# 13-UART_CAN_IO.net
KiCad netlist of a schematic drawn in Altium Designer
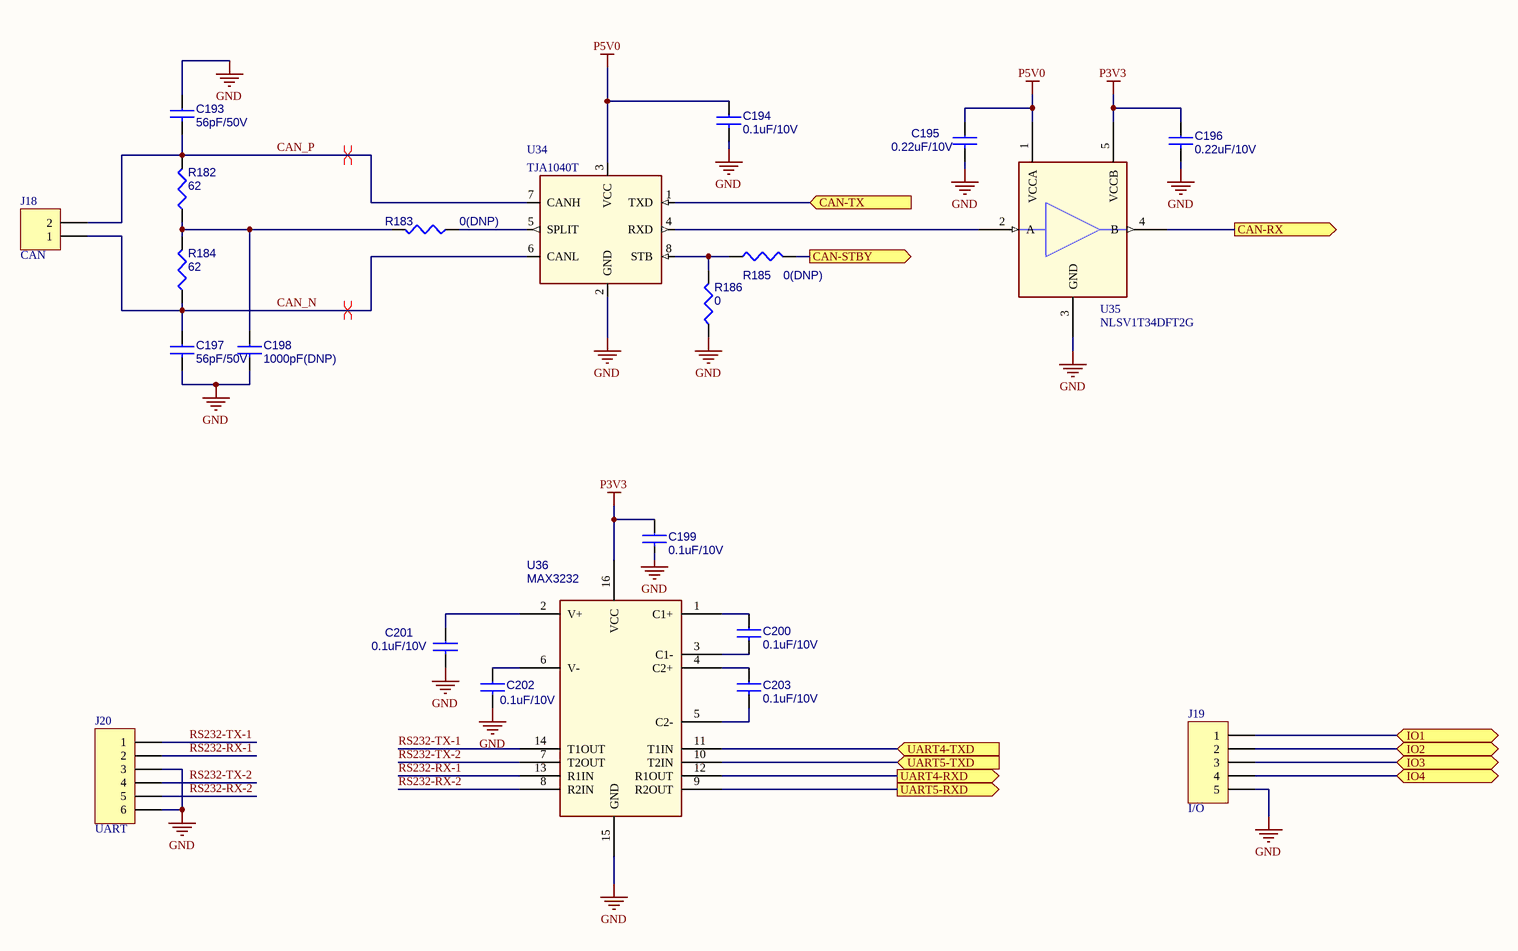
[diagram p0: 13-UART_CAN_IO.SchDoc]

(export (version "E")
  (design (tool "Eeschema 10.0.6"))
  (components
    (comp (ref "C193") (value "56pF/50V") (libsource (lib "*") (part "P_CAP NP")))
    (comp (ref "C194") (value "0.1uF/10V") (libsource (lib "*") (part "P_CAP NP")))
    (comp (ref "C195") (value "0.22uF/10V") (libsource (lib "*") (part "P_CAP NP")))
    (comp (ref "C196") (value "0.22uF/10V") (libsource (lib "*") (part "P_CAP NP")))
    (comp (ref "C197") (value "56pF/50V") (libsource (lib "*") (part "P_CAP NP")))
    (comp (ref "C198") (value "1000pF(DNP)") (libsource (lib "*") (part "P_CAP NP")))
    (comp (ref "C199") (value "0.1uF/10V") (libsource (lib "*") (part "CAP")))
    (comp (ref "C200") (value "0.1uF/10V") (libsource (lib "*") (part "CAP")))
    (comp (ref "C201") (value "0.1uF/10V") (libsource (lib "*") (part "CAP")))
    (comp (ref "C202") (value "0.1uF/10V") (libsource (lib "*") (part "CAP")))
    (comp (ref "C203") (value "0.1uF/10V") (libsource (lib "*") (part "CAP")))
    (comp (ref "J18")
      (value "CAN")
      (footprint "CON-2PIN")
      (description "Header, 2-Pin")
      (fields (field (name "PUBLISHER") "Altium Limited"))
      (libsource (lib "Miscellaneous Connectors") (part "Header 2"))
    )
    (comp (ref "J19")
      (value "I/O")
      (footprint "CON-5PIN")
      (description "Header, 5-Pin")
      (fields (field (name "PUBLISHER") "Altium Limited"))
      (libsource (lib "Miscellaneous Connectors") (part "Header 5"))
    )
    (comp (ref "J20")
      (value "UART")
      (footprint "CON-6PIN")
      (description "Header, 6-Pin")
      (fields (field (name "PUBLISHER") "Altium Limited"))
      (libsource (lib "Miscellaneous Connectors") (part "Header 6"))
    )
    (comp (ref "R182") (value "62") (footprint "0402") (libsource (lib "*") (part "P_R")))
    (comp (ref "R183") (value "0(DNP)") (footprint "0402") (libsource (lib "*") (part "P_R")))
    (comp (ref "R184") (value "62") (footprint "0402") (libsource (lib "*") (part "P_R")))
    (comp (ref "R185") (value "0(DNP)") (footprint "0402") (libsource (lib "*") (part "P_R")))
    (comp (ref "R186") (value "0") (footprint "0402") (libsource (lib "*") (part "P_R")))
    (comp (ref "U34")
      (value "TJA1040T")
      (footprint "SO8")
      (description "IC XCVR CAN HS 5V SO8")
      (libsource (lib "*") (part "TJA1040T_SO_8P"))
    )
    (comp (ref "U35")
      (value "NLSV1T34DFT2G")
      (footprint "SC70")
      (libsource (lib "Schlib") (part "NLSV1T34DFT2G"))
    )
    (comp (ref "U36") (value "MAX3232") (footprint "SO-16") (libsource (lib "*") (part "MAX3232")))
  )
  (nets
    (net (code "1") (name "/CAN-RX") (class "Default")
      (node (ref "U35") (pin "4") (pinfunction "B_4") (pintype "output"))
    )
    (net (code "2") (name "/CAN-STBY") (class "Default")
      (node (ref "R185") (pin "1") (pinfunction "1_1") (pintype "passive"))
    )
    (net (code "3") (name "/CAN-TX") (class "Default")
      (node (ref "U34") (pin "1") (pinfunction "TXD_1") (pintype "input"))
    )
    (net (code "4") (name "/CAN_N") (class "Default")
      (node (ref "C197") (pin "1") (pinfunction "1_1") (pintype "passive"))
      (node (ref "J18") (pin "1") (pinfunction "1_1") (pintype "passive"))
      (node (ref "R184") (pin "2") (pinfunction "2_2") (pintype "passive"))
      (node (ref "U34") (pin "6") (pinfunction "CANL_6") (pintype "bidirectional"))
    )
    (net (code "5") (name "/CAN_P") (class "Default")
      (node (ref "C193") (pin "2") (pinfunction "2_2") (pintype "passive"))
      (node (ref "J18") (pin "2") (pinfunction "2_2") (pintype "passive"))
      (node (ref "R182") (pin "1") (pinfunction "1_1") (pintype "passive"))
      (node (ref "U34") (pin "7") (pinfunction "CANH_7") (pintype "bidirectional"))
    )
    (net (code "6") (name "/IO1") (class "Default")
      (node (ref "J19") (pin "1") (pinfunction "1_1") (pintype "passive"))
    )
    (net (code "7") (name "/IO2") (class "Default")
      (node (ref "J19") (pin "2") (pinfunction "2_2") (pintype "passive"))
    )
    (net (code "8") (name "/IO3") (class "Default")
      (node (ref "J19") (pin "3") (pinfunction "3_3") (pintype "passive"))
    )
    (net (code "9") (name "/IO4") (class "Default")
      (node (ref "J19") (pin "4") (pinfunction "4_4") (pintype "passive"))
    )
    (net (code "10") (name "/RS232-RX-1") (class "Default")
      (node (ref "J20") (pin "2") (pinfunction "2_2") (pintype "passive"))
      (node (ref "U36") (pin "13") (pinfunction "R1IN_13") (pintype "passive"))
    )
    (net (code "11") (name "/RS232-RX-2") (class "Default")
      (node (ref "J20") (pin "5") (pinfunction "5_5") (pintype "passive"))
      (node (ref "U36") (pin "8") (pinfunction "R2IN_8") (pintype "passive"))
    )
    (net (code "12") (name "/RS232-TX-1") (class "Default")
      (node (ref "J20") (pin "1") (pinfunction "1_1") (pintype "passive"))
      (node (ref "U36") (pin "14") (pinfunction "T1OUT_14") (pintype "passive"))
    )
    (net (code "13") (name "/RS232-TX-2") (class "Default")
      (node (ref "J20") (pin "4") (pinfunction "4_4") (pintype "passive"))
      (node (ref "U36") (pin "7") (pinfunction "T2OUT_7") (pintype "passive"))
    )
    (net (code "14") (name "/UART4-RXD") (class "Default")
      (node (ref "U36") (pin "12") (pinfunction "R1OUT_12") (pintype "passive"))
    )
    (net (code "15") (name "/UART4-TXD") (class "Default")
      (node (ref "U36") (pin "11") (pinfunction "T1IN_11") (pintype "passive"))
    )
    (net (code "16") (name "/UART5-RXD") (class "Default")
      (node (ref "U36") (pin "9") (pinfunction "R2OUT_9") (pintype "passive"))
    )
    (net (code "17") (name "/UART5-TXD") (class "Default")
      (node (ref "U36") (pin "10") (pinfunction "T2IN_10") (pintype "passive"))
    )
    (net (code "18") (name "GND") (class "Default")
      (node (ref "C193") (pin "1") (pinfunction "1_1") (pintype "passive"))
      (node (ref "C194") (pin "2") (pinfunction "2_2") (pintype "passive"))
      (node (ref "C195") (pin "2") (pinfunction "2_2") (pintype "passive"))
      (node (ref "C196") (pin "2") (pinfunction "2_2") (pintype "passive"))
      (node (ref "C197") (pin "2") (pinfunction "2_2") (pintype "passive"))
      (node (ref "C198") (pin "2") (pinfunction "2_2") (pintype "passive"))
      (node (ref "C199") (pin "2") (pinfunction "2_2") (pintype "passive"))
      (node (ref "C201") (pin "2") (pinfunction "2_2") (pintype "passive"))
      (node (ref "C202") (pin "2") (pinfunction "2_2") (pintype "passive"))
      (node (ref "J19") (pin "5") (pinfunction "5_5") (pintype "passive"))
      (node (ref "J20") (pin "3") (pinfunction "3_3") (pintype "passive"))
      (node (ref "J20") (pin "6") (pinfunction "6_6") (pintype "passive"))
      (node (ref "R186") (pin "2") (pinfunction "2_2") (pintype "passive"))
      (node (ref "U34") (pin "2") (pinfunction "GND_2") (pintype "power_in"))
      (node (ref "U35") (pin "3") (pinfunction "GND_3") (pintype "power_in"))
      (node (ref "U36") (pin "15") (pinfunction "GND_15") (pintype "passive"))
    )
    (net (code "19") (name "Net-(C198-Pad1)") (class "Default")
      (node (ref "C198") (pin "1") (pinfunction "1_1") (pintype "passive"))
      (node (ref "R182") (pin "2") (pinfunction "2_2") (pintype "passive"))
      (node (ref "R183") (pin "1") (pinfunction "1_1") (pintype "passive"))
      (node (ref "R184") (pin "1") (pinfunction "1_1") (pintype "passive"))
    )
    (net (code "20") (name "Net-(U34-RXD)") (class "Default")
      (node (ref "U34") (pin "4") (pinfunction "RXD_4") (pintype "output"))
      (node (ref "U35") (pin "2") (pinfunction "A_2") (pintype "input"))
    )
    (net (code "21") (name "Net-(U34-SPLIT)") (class "Default")
      (node (ref "R183") (pin "2") (pinfunction "2_2") (pintype "passive"))
      (node (ref "U34") (pin "5") (pinfunction "SPLIT_5") (pintype "output"))
    )
    (net (code "22") (name "Net-(U34-STB)") (class "Default")
      (node (ref "R185") (pin "2") (pinfunction "2_2") (pintype "passive"))
      (node (ref "R186") (pin "1") (pinfunction "1_1") (pintype "passive"))
      (node (ref "U34") (pin "8") (pinfunction "STB_8") (pintype "input"))
    )
    (net (code "23") (name "Net-(U36-C1+)") (class "Default")
      (node (ref "C200") (pin "1") (pinfunction "1_1") (pintype "passive"))
      (node (ref "U36") (pin "1") (pinfunction "C1+_1") (pintype "passive"))
    )
    (net (code "24") (name "Net-(U36-C1-)") (class "Default")
      (node (ref "C200") (pin "2") (pinfunction "2_2") (pintype "passive"))
      (node (ref "U36") (pin "3") (pinfunction "C1-_3") (pintype "passive"))
    )
    (net (code "25") (name "Net-(U36-C2+)") (class "Default")
      (node (ref "C203") (pin "1") (pinfunction "1_1") (pintype "passive"))
      (node (ref "U36") (pin "4") (pinfunction "C2+_4") (pintype "passive"))
    )
    (net (code "26") (name "Net-(U36-C2-)") (class "Default")
      (node (ref "C203") (pin "2") (pinfunction "2_2") (pintype "passive"))
      (node (ref "U36") (pin "5") (pinfunction "C2-_5") (pintype "passive"))
    )
    (net (code "27") (name "Net-(U36-V+)") (class "Default")
      (node (ref "C201") (pin "1") (pinfunction "1_1") (pintype "passive"))
      (node (ref "U36") (pin "2") (pinfunction "V+_2") (pintype "passive"))
    )
    (net (code "28") (name "Net-(U36-V-)") (class "Default")
      (node (ref "C202") (pin "1") (pinfunction "1_1") (pintype "passive"))
      (node (ref "U36") (pin "6") (pinfunction "V-_6") (pintype "passive"))
    )
    (net (code "29") (name "P3V3") (class "Default")
      (node (ref "C196") (pin "1") (pinfunction "1_1") (pintype "passive"))
      (node (ref "C199") (pin "1") (pinfunction "1_1") (pintype "passive"))
      (node (ref "U35") (pin "5") (pinfunction "VCCB_5") (pintype "power_in"))
      (node (ref "U36") (pin "16") (pinfunction "VCC_16") (pintype "passive"))
    )
    (net (code "30") (name "P5V0") (class "Default")
      (node (ref "C194") (pin "1") (pinfunction "1_1") (pintype "passive"))
      (node (ref "C195") (pin "1") (pinfunction "1_1") (pintype "passive"))
      (node (ref "U34") (pin "3") (pinfunction "VCC_3") (pintype "power_in"))
      (node (ref "U35") (pin "1") (pinfunction "VCCA_1") (pintype "power_in"))
    )
  )
)
